# RS232v20_9x.net
KiCad netlist of a schematic drawn in EAGLE
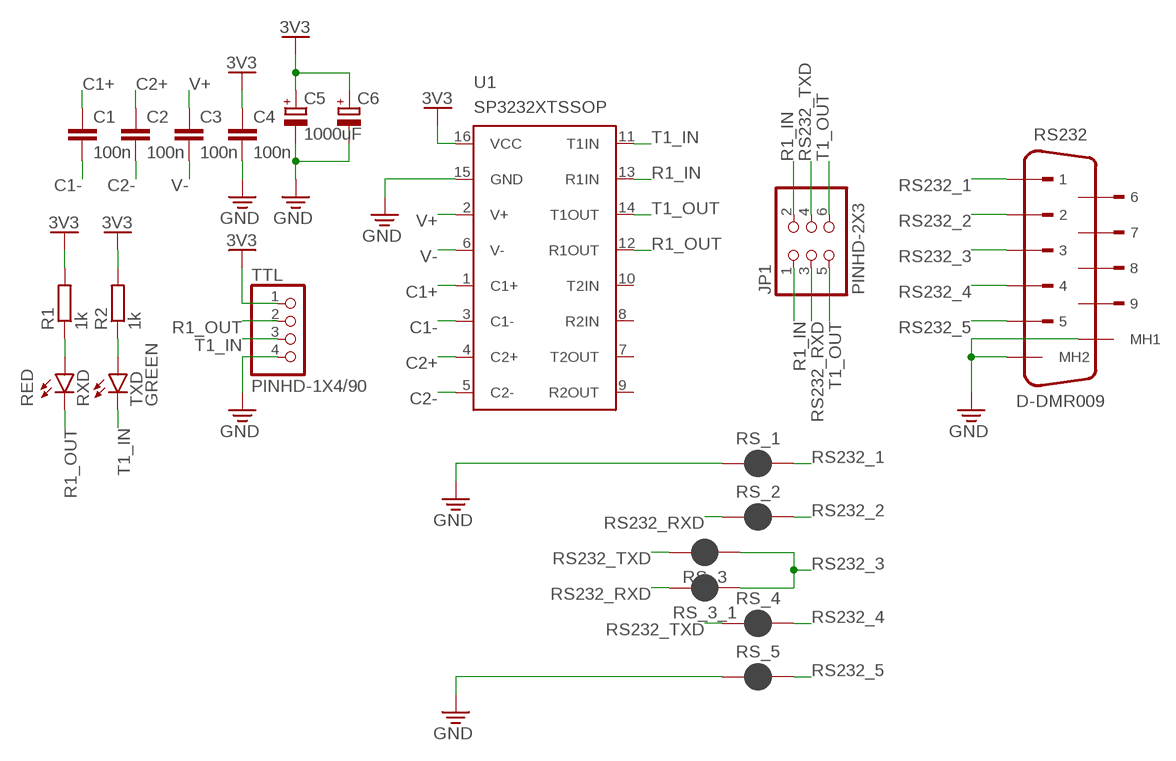
[diagram p0: schematic, sheet 1]

(export (version "E")
  (design (tool "Eeschema 10.0.6"))
  (components
    (comp (ref "C1")
      (value "100n")
      (footprint "eagle-import:C0402")
      (libsource (lib "eagle-import") (part "C-EUC0402"))
    )
    (comp (ref "C2")
      (value "100n")
      (footprint "eagle-import:C0402")
      (libsource (lib "eagle-import") (part "C-EUC0402"))
    )
    (comp (ref "C3")
      (value "100n")
      (footprint "eagle-import:C0402")
      (libsource (lib "eagle-import") (part "C-EUC0402"))
    )
    (comp (ref "C4")
      (value "100n")
      (footprint "eagle-import:C0402")
      (libsource (lib "eagle-import") (part "C-EUC0402"))
    )
    (comp (ref "C5")
      (value "1000uF")
      (footprint "eagle-import:140CLH-1010")
      (libsource (lib "eagle-import") (part "CPOL-EU140CLH-1010"))
    )
    (comp (ref "C6")
      (value "C-POL_RADIAL-11MM-DIA")
      (footprint "eagle-import:CAPPRD508W65D1000H1100B")
      (libsource (lib "eagle-import") (part "C-POLRADIAL-11MM-DIA_"))
    )
    (comp (ref "JP1")
      (value "PINHD-2X3")
      (footprint "eagle-import:2X03")
      (fields (field (name "MANUFACTURER") "Generic"))
      (libsource (lib "eagle-import") (part "PINHD-2X3"))
    )
    (comp (ref "R1")
      (value "1k")
      (footprint "eagle-import:R0402")
      (libsource (lib "eagle-import") (part "R-EU_R0402"))
    )
    (comp (ref "R2")
      (value "1k")
      (footprint "eagle-import:R0402")
      (libsource (lib "eagle-import") (part "R-EU_R0402"))
    )
    (comp (ref "RS232")
      (value "D-DMR009")
      (footprint "eagle-import:5747840-4")
      (fields (field (name "MANUFACTURER") "TE Connectivity") (field (name "MPN") "5747840-4"))
      (libsource (lib "eagle-import") (part "5747840{dblquote}"))
    )
    (comp (ref "RS_1")
      (value "JUMPER-SMT_2_NC_PASTE_SILK")
      (footprint "eagle-import:SMT-JUMPER_2_NC_PASTE_SILK")
      (libsource (lib "eagle-import") (part "JUMPER-SMT_2_NC_PASTE_SILK"))
    )
    (comp (ref "RS_2")
      (value "JUMPER-SMT_2_NC_PASTE_SILK")
      (footprint "eagle-import:SMT-JUMPER_2_NC_PASTE_SILK")
      (libsource (lib "eagle-import") (part "JUMPER-SMT_2_NC_PASTE_SILK"))
    )
    (comp (ref "RS_3")
      (value "JUMPER-SMT_2_NC_PASTE_SILK")
      (footprint "eagle-import:SMT-JUMPER_2_NC_PASTE_SILK")
      (libsource (lib "eagle-import") (part "JUMPER-SMT_2_NC_PASTE_SILK"))
    )
    (comp (ref "RS_3_1")
      (value "JUMPER-SMT_2_NC_PASTE_SILK")
      (footprint "eagle-import:SMT-JUMPER_2_NC_PASTE_SILK")
      (libsource (lib "eagle-import") (part "JUMPER-SMT_2_NC_PASTE_SILK"))
    )
    (comp (ref "RS_4")
      (value "JUMPER-SMT_2_NC_PASTE_SILK")
      (footprint "eagle-import:SMT-JUMPER_2_NC_PASTE_SILK")
      (libsource (lib "eagle-import") (part "JUMPER-SMT_2_NC_PASTE_SILK"))
    )
    (comp (ref "RS_5")
      (value "JUMPER-SMT_2_NC_PASTE_SILK")
      (footprint "eagle-import:SMT-JUMPER_2_NC_PASTE_SILK")
      (libsource (lib "eagle-import") (part "JUMPER-SMT_2_NC_PASTE_SILK"))
    )
    (comp (ref "RXD")
      (value "RED")
      (footprint "eagle-import:CHIP-LED0603")
      (libsource (lib "eagle-import") (part "LEDCHIP-LED0603"))
    )
    (comp (ref "TTL")
      (value "PINHD-1X4/90")
      (footprint "eagle-import:1X04_90")
      (fields (field (name "MANUFACTURER") "Generic"))
      (libsource (lib "eagle-import") (part "PINHD-1X4/90"))
    )
    (comp (ref "TXD")
      (value "GREEN")
      (footprint "eagle-import:CHIP-LED0603")
      (libsource (lib "eagle-import") (part "LEDCHIP-LED0603"))
    )
    (comp (ref "U1")
      (value "SP3232XTSSOP")
      (footprint "eagle-import:TSSOP16")
      (libsource (lib "eagle-import") (part "SP3232XTSSOP"))
    )
  )
  (nets
    (net (code "1") (name "/C1+") (class "Default")
      (node (ref "C1") (pin "1") (pinfunction "1_1") (pintype "passive"))
      (node (ref "U1") (pin "1") (pinfunction "C1+_1") (pintype "bidirectional"))
    )
    (net (code "2") (name "/C1-") (class "Default")
      (node (ref "C1") (pin "2") (pinfunction "2_2") (pintype "passive"))
      (node (ref "U1") (pin "3") (pinfunction "C1-_3") (pintype "bidirectional"))
    )
    (net (code "3") (name "/C2+") (class "Default")
      (node (ref "C2") (pin "1") (pinfunction "1_1") (pintype "passive"))
      (node (ref "U1") (pin "4") (pinfunction "C2+_4") (pintype "bidirectional"))
    )
    (net (code "4") (name "/C2-") (class "Default")
      (node (ref "C2") (pin "2") (pinfunction "2_2") (pintype "passive"))
      (node (ref "U1") (pin "5") (pinfunction "C2-_5") (pintype "bidirectional"))
    )
    (net (code "5") (name "/R1_IN") (class "Default")
      (node (ref "JP1") (pin "1") (pinfunction "1_1") (pintype "passive"))
      (node (ref "JP1") (pin "2") (pinfunction "2_2") (pintype "passive"))
      (node (ref "U1") (pin "13") (pinfunction "R1IN_13") (pintype "input"))
    )
    (net (code "6") (name "/R1_OUT") (class "Default")
      (node (ref "RXD") (pin "C") (pinfunction "C_C") (pintype "passive"))
      (node (ref "TTL") (pin "2") (pinfunction "2_2") (pintype "passive"))
      (node (ref "U1") (pin "12") (pinfunction "R1OUT_12") (pintype "output"))
    )
    (net (code "7") (name "/RS232_1") (class "Default")
      (node (ref "RS232") (pin "1") (pinfunction "1_1") (pintype "passive"))
      (node (ref "RS_1") (pin "2") (pinfunction "2_2") (pintype "passive"))
    )
    (net (code "8") (name "/RS232_2") (class "Default")
      (node (ref "RS232") (pin "2") (pinfunction "2_2") (pintype "passive"))
      (node (ref "RS_2") (pin "2") (pinfunction "2_2") (pintype "passive"))
    )
    (net (code "9") (name "/RS232_3") (class "Default")
      (node (ref "RS232") (pin "3") (pinfunction "3_3") (pintype "passive"))
      (node (ref "RS_3") (pin "1") (pinfunction "1_1") (pintype "passive"))
      (node (ref "RS_3_1") (pin "1") (pinfunction "1_1") (pintype "passive"))
    )
    (net (code "10") (name "/RS232_4") (class "Default")
      (node (ref "RS232") (pin "4") (pinfunction "4_4") (pintype "passive"))
      (node (ref "RS_4") (pin "2") (pinfunction "2_2") (pintype "passive"))
    )
    (net (code "11") (name "/RS232_5") (class "Default")
      (node (ref "RS232") (pin "5") (pinfunction "5_5") (pintype "passive"))
      (node (ref "RS_5") (pin "2") (pinfunction "2_2") (pintype "passive"))
    )
    (net (code "12") (name "/RS232_RXD") (class "Default")
      (node (ref "JP1") (pin "3") (pinfunction "3_3") (pintype "passive"))
      (node (ref "RS_2") (pin "1") (pinfunction "1_1") (pintype "passive"))
      (node (ref "RS_3_1") (pin "2") (pinfunction "2_2") (pintype "passive"))
    )
    (net (code "13") (name "/RS232_TXD") (class "Default")
      (node (ref "JP1") (pin "4") (pinfunction "4_4") (pintype "passive"))
      (node (ref "RS_3") (pin "2") (pinfunction "2_2") (pintype "passive"))
      (node (ref "RS_4") (pin "1") (pinfunction "1_1") (pintype "passive"))
    )
    (net (code "14") (name "/T1_IN") (class "Default")
      (node (ref "TTL") (pin "3") (pinfunction "3_3") (pintype "passive"))
      (node (ref "TXD") (pin "C") (pinfunction "C_C") (pintype "passive"))
      (node (ref "U1") (pin "11") (pinfunction "T1IN_11") (pintype "input"))
    )
    (net (code "15") (name "/T1_OUT") (class "Default")
      (node (ref "JP1") (pin "5") (pinfunction "5_5") (pintype "passive"))
      (node (ref "JP1") (pin "6") (pinfunction "6_6") (pintype "passive"))
      (node (ref "U1") (pin "14") (pinfunction "T1OUT_14") (pintype "output"))
    )
    (net (code "16") (name "/V+") (class "Default")
      (node (ref "C3") (pin "1") (pinfunction "1_1") (pintype "passive"))
      (node (ref "U1") (pin "2") (pinfunction "V+_2") (pintype "power_in"))
    )
    (net (code "17") (name "/V-") (class "Default")
      (node (ref "C3") (pin "2") (pinfunction "2_2") (pintype "passive"))
      (node (ref "U1") (pin "6") (pinfunction "V-_6") (pintype "power_in"))
    )
    (net (code "18") (name "3V3") (class "Default")
      (node (ref "C4") (pin "1") (pinfunction "1_1") (pintype "passive"))
      (node (ref "C5") (pin "+") (pinfunction "+_+") (pintype "passive"))
      (node (ref "C6") (pin "1") (pinfunction "+_1") (pintype "passive"))
      (node (ref "R1") (pin "2") (pinfunction "2_2") (pintype "passive"))
      (node (ref "R2") (pin "2") (pinfunction "2_2") (pintype "passive"))
      (node (ref "TTL") (pin "1") (pinfunction "1_1") (pintype "passive"))
      (node (ref "U1") (pin "16") (pinfunction "VCC_16") (pintype "power_in"))
    )
    (net (code "19") (name "GND") (class "Default")
      (node (ref "C4") (pin "2") (pinfunction "2_2") (pintype "passive"))
      (node (ref "C5") (pin "-") (pinfunction "-_-") (pintype "passive"))
      (node (ref "C6") (pin "2") (pinfunction "-_2") (pintype "passive"))
      (node (ref "RS232") (pin "MH1") (pinfunction "MH2_MH1") (pintype "power_in"))
      (node (ref "RS232") (pin "MH2") (pinfunction "MH1_MH2") (pintype "power_in"))
      (node (ref "RS_1") (pin "1") (pinfunction "1_1") (pintype "passive"))
      (node (ref "RS_5") (pin "1") (pinfunction "1_1") (pintype "passive"))
      (node (ref "TTL") (pin "4") (pinfunction "4_4") (pintype "passive"))
      (node (ref "U1") (pin "15") (pinfunction "GND_15") (pintype "power_in"))
    )
    (net (code "20") (name "Net-(R1-Pad1)") (class "Default")
      (node (ref "R1") (pin "1") (pinfunction "1_1") (pintype "passive"))
      (node (ref "RXD") (pin "A") (pinfunction "A_A") (pintype "passive"))
    )
    (net (code "21") (name "Net-(R2-Pad1)") (class "Default")
      (node (ref "R2") (pin "1") (pinfunction "1_1") (pintype "passive"))
      (node (ref "TXD") (pin "A") (pinfunction "A_A") (pintype "passive"))
    )
    (net (code "22") (name "unconnected-(RS232-Pad6)") (class "Default")
      (node (ref "RS232") (pin "6") (pinfunction "6_6") (pintype "passive"))
    )
    (net (code "23") (name "unconnected-(RS232-Pad7)") (class "Default")
      (node (ref "RS232") (pin "7") (pinfunction "7_7") (pintype "passive"))
    )
    (net (code "24") (name "unconnected-(RS232-Pad8)") (class "Default")
      (node (ref "RS232") (pin "8") (pinfunction "8_8") (pintype "passive"))
    )
    (net (code "25") (name "unconnected-(RS232-Pad9)") (class "Default")
      (node (ref "RS232") (pin "9") (pinfunction "9_9") (pintype "passive"))
    )
    (net (code "26") (name "unconnected-(U1-R2IN-Pad8)") (class "Default")
      (node (ref "U1") (pin "8") (pinfunction "R2IN_8") (pintype "input"))
    )
    (net (code "27") (name "unconnected-(U1-R2OUT-Pad9)") (class "Default")
      (node (ref "U1") (pin "9") (pinfunction "R2OUT_9") (pintype "output"))
    )
    (net (code "28") (name "unconnected-(U1-T2IN-Pad10)") (class "Default")
      (node (ref "U1") (pin "10") (pinfunction "T2IN_10") (pintype "input"))
    )
    (net (code "29") (name "unconnected-(U1-T2OUT-Pad7)") (class "Default")
      (node (ref "U1") (pin "7") (pinfunction "T2OUT_7") (pintype "output"))
    )
  )
)
